# avoccado-avr-pcb-faye.net
KiCad netlist of a schematic drawn in EAGLE
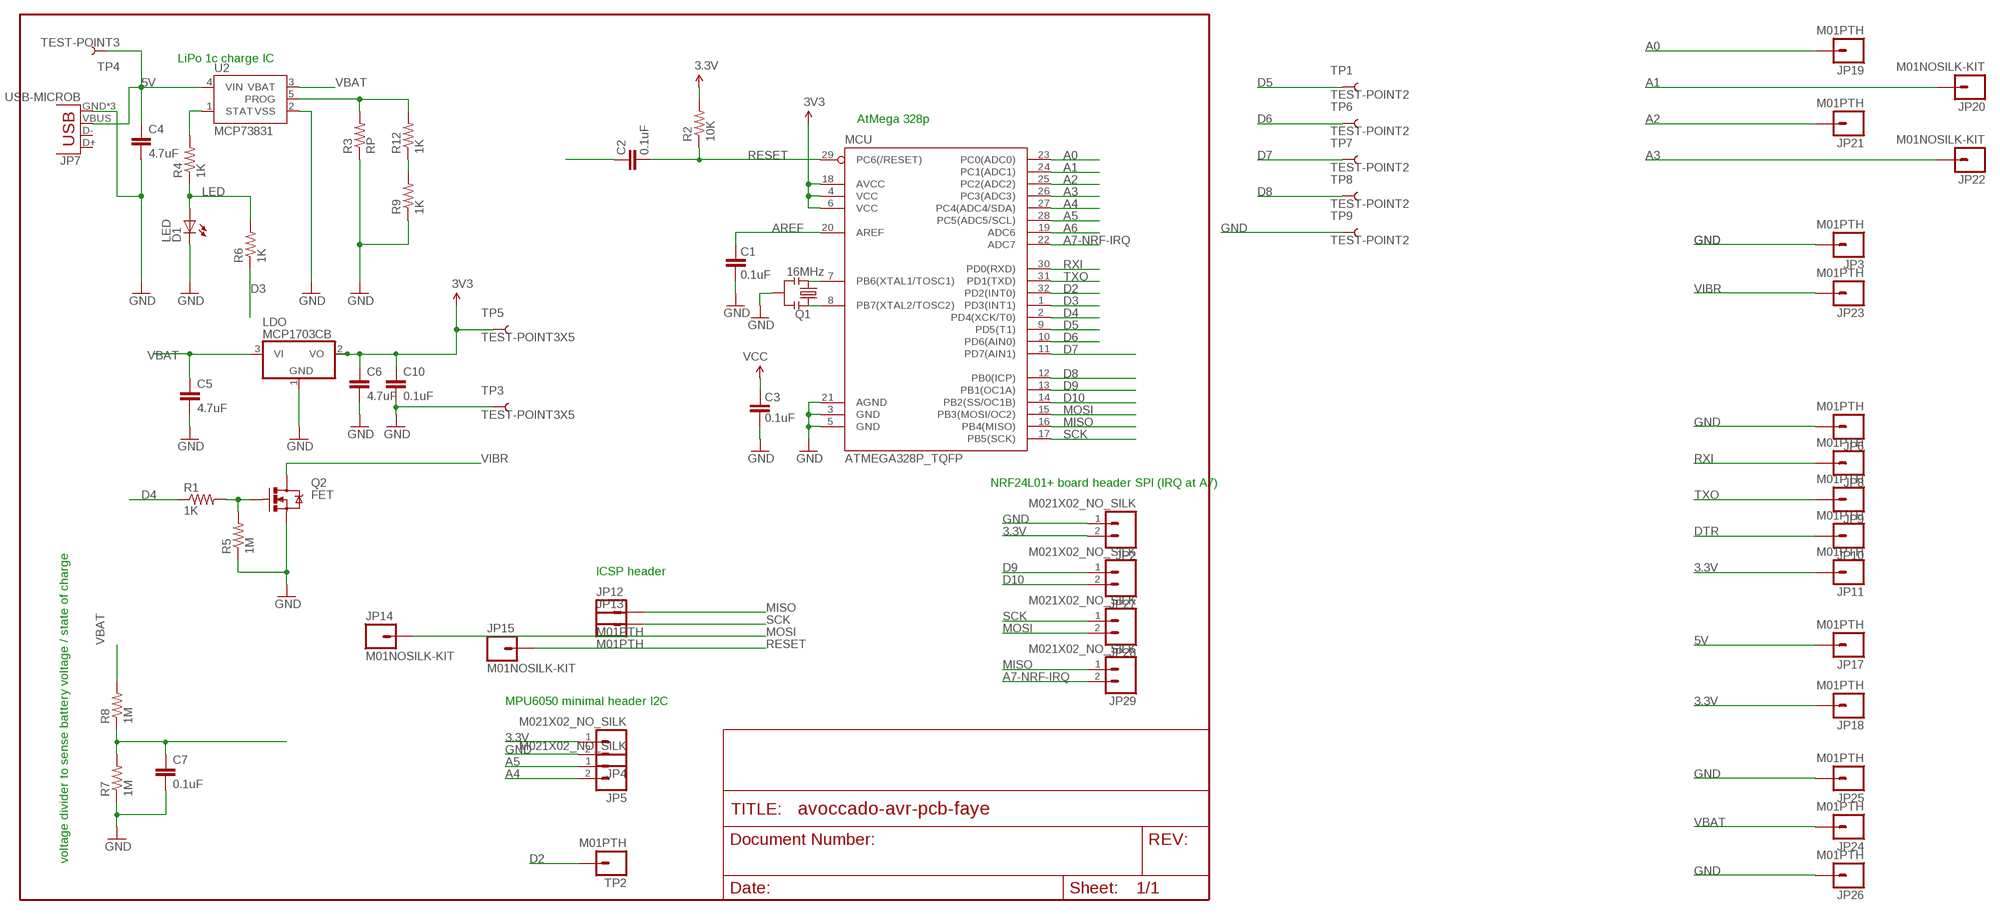
[diagram p0: schematic, sheet 1]

(export (version "E")
  (design (tool "Eeschema 10.0.6"))
  (components
    (comp (ref "C1")
      (value "0.1uF")
      (footprint "eagle-import:C0402")
      (libsource (lib "eagle-import") (part "CAP0402"))
    )
    (comp (ref "C2")
      (value "0.1uF")
      (footprint "eagle-import:C0402")
      (libsource (lib "eagle-import") (part "CAP0402"))
    )
    (comp (ref "C3")
      (value "0.1uF")
      (footprint "eagle-import:C0402")
      (libsource (lib "eagle-import") (part "CAP0402"))
    )
    (comp (ref "C4")
      (value "4.7uF")
      (footprint "eagle-import:0603-CAP")
      (libsource (lib "eagle-import") (part "4.7UF-6.3V-10%(0603)0603"))
    )
    (comp (ref "C5")
      (value "4.7uF")
      (footprint "eagle-import:0603-CAP")
      (libsource (lib "eagle-import") (part "4.7UF-6.3V-10%(0603)0603"))
    )
    (comp (ref "C6")
      (value "4.7uF")
      (footprint "eagle-import:0603-CAP")
      (libsource (lib "eagle-import") (part "4.7UF-6.3V-10%(0603)0603"))
    )
    (comp (ref "C7")
      (value "0.1uF")
      (footprint "eagle-import:C0402")
      (libsource (lib "eagle-import") (part "CAP0402"))
    )
    (comp (ref "C10")
      (value "0.1uF")
      (footprint "eagle-import:C0402")
      (libsource (lib "eagle-import") (part "CAP0402"))
    )
    (comp (ref "D1")
      (value "LED")
      (footprint "eagle-import:LED-0603")
      (libsource (lib "eagle-import") (part "LED0603"))
    )
    (comp (ref "JP2")
      (value "M021X02_NO_SILK")
      (footprint "eagle-import:1X02_NO_SILK")
      (libsource (lib "eagle-import") (part "M021X02_NO_SILK"))
    )
    (comp (ref "JP3")
      (value "M01PTH")
      (footprint "eagle-import:1X01")
      (libsource (lib "eagle-import") (part "M01PTH"))
    )
    (comp (ref "JP4")
      (value "M021X02_NO_SILK")
      (footprint "eagle-import:1X02_NO_SILK")
      (libsource (lib "eagle-import") (part "M021X02_NO_SILK"))
    )
    (comp (ref "JP5")
      (value "M021X02_NO_SILK")
      (footprint "eagle-import:1X02_NO_SILK")
      (libsource (lib "eagle-import") (part "M021X02_NO_SILK"))
    )
    (comp (ref "JP6")
      (value "M01PTH")
      (footprint "eagle-import:1X01")
      (libsource (lib "eagle-import") (part "M01PTH"))
    )
    (comp (ref "JP7")
      (value "USB-MICROB")
      (footprint "eagle-import:USB-MICROB")
      (libsource (lib "eagle-import") (part "USB-MICROB"))
    )
    (comp (ref "JP8")
      (value "M01PTH")
      (footprint "eagle-import:1X01")
      (libsource (lib "eagle-import") (part "M01PTH"))
    )
    (comp (ref "JP9")
      (value "M01PTH")
      (footprint "eagle-import:1X01")
      (libsource (lib "eagle-import") (part "M01PTH"))
    )
    (comp (ref "JP10")
      (value "M01PTH")
      (footprint "eagle-import:1X01")
      (libsource (lib "eagle-import") (part "M01PTH"))
    )
    (comp (ref "JP11")
      (value "M01PTH")
      (footprint "eagle-import:1X01")
      (libsource (lib "eagle-import") (part "M01PTH"))
    )
    (comp (ref "JP12")
      (value "M01PTH")
      (footprint "eagle-import:1X01")
      (libsource (lib "eagle-import") (part "M01PTH"))
    )
    (comp (ref "JP13")
      (value "M01PTH")
      (footprint "eagle-import:1X01")
      (libsource (lib "eagle-import") (part "M01PTH"))
    )
    (comp (ref "JP14")
      (value "M01NOSILK-KIT")
      (footprint "eagle-import:1X01NS-KIT")
      (libsource (lib "eagle-import") (part "M01NOSILK-KIT"))
    )
    (comp (ref "JP15")
      (value "M01NOSILK-KIT")
      (footprint "eagle-import:1X01NS-KIT")
      (libsource (lib "eagle-import") (part "M01NOSILK-KIT"))
    )
    (comp (ref "JP17")
      (value "M01PTH")
      (footprint "eagle-import:1X01")
      (libsource (lib "eagle-import") (part "M01PTH"))
    )
    (comp (ref "JP18")
      (value "M01PTH")
      (footprint "eagle-import:1X01")
      (libsource (lib "eagle-import") (part "M01PTH"))
    )
    (comp (ref "JP19")
      (value "M01PTH")
      (footprint "eagle-import:1X01")
      (libsource (lib "eagle-import") (part "M01PTH"))
    )
    (comp (ref "JP20")
      (value "M01NOSILK-KIT")
      (footprint "eagle-import:1X01NS-KIT")
      (libsource (lib "eagle-import") (part "M01NOSILK-KIT"))
    )
    (comp (ref "JP21")
      (value "M01PTH")
      (footprint "eagle-import:1X01")
      (libsource (lib "eagle-import") (part "M01PTH"))
    )
    (comp (ref "JP22")
      (value "M01NOSILK-KIT")
      (footprint "eagle-import:1X01NS-KIT")
      (libsource (lib "eagle-import") (part "M01NOSILK-KIT"))
    )
    (comp (ref "JP23")
      (value "M01PTH")
      (footprint "eagle-import:1X01")
      (libsource (lib "eagle-import") (part "M01PTH"))
    )
    (comp (ref "JP24")
      (value "M01PTH")
      (footprint "eagle-import:1X01")
      (libsource (lib "eagle-import") (part "M01PTH"))
    )
    (comp (ref "JP25")
      (value "M01PTH")
      (footprint "eagle-import:1X01")
      (libsource (lib "eagle-import") (part "M01PTH"))
    )
    (comp (ref "JP26")
      (value "M01PTH")
      (footprint "eagle-import:1X01")
      (libsource (lib "eagle-import") (part "M01PTH"))
    )
    (comp (ref "JP27")
      (value "M021X02_NO_SILK")
      (footprint "eagle-import:1X02_NO_SILK")
      (libsource (lib "eagle-import") (part "M021X02_NO_SILK"))
    )
    (comp (ref "JP28")
      (value "M021X02_NO_SILK")
      (footprint "eagle-import:1X02_NO_SILK")
      (libsource (lib "eagle-import") (part "M021X02_NO_SILK"))
    )
    (comp (ref "JP29")
      (value "M021X02_NO_SILK")
      (footprint "eagle-import:1X02_NO_SILK")
      (libsource (lib "eagle-import") (part "M021X02_NO_SILK"))
    )
    (comp (ref "LDO")
      (value "MCP1703CB")
      (footprint "eagle-import:SOT23")
      (libsource (lib "eagle-import") (part "MCP1703CB"))
    )
    (comp (ref "MCU")
      (value "ATMEGA328P_TQFP")
      (footprint "eagle-import:TQFP32-08")
      (libsource (lib "eagle-import") (part "ATMEGA328P_TQFP"))
    )
    (comp (ref "Q1")
      (value "16MHz")
      (footprint "eagle-import:RESONATOR-SMD")
      (libsource (lib "eagle-import") (part "RESONATORSMD"))
    )
    (comp (ref "Q2")
      (value "FET")
      (footprint "eagle-import:SOT23-3")
      (libsource (lib "eagle-import") (part "MOSFET-NCHANNELBSS123LT1G"))
    )
    (comp (ref "R1")
      (value "1K")
      (footprint "eagle-import:0603-RES")
      (libsource (lib "eagle-import") (part "RESISTOR0603"))
    )
    (comp (ref "R2")
      (value "10K")
      (footprint "eagle-import:0603-RES")
      (libsource (lib "eagle-import") (part "RESISTOR0603"))
    )
    (comp (ref "R3")
      (value "RP")
      (footprint "eagle-import:0603-RES")
      (libsource (lib "eagle-import") (part "RESISTOR0603"))
    )
    (comp (ref "R4")
      (value "1K")
      (footprint "eagle-import:0603-RES")
      (libsource (lib "eagle-import") (part "RESISTOR0603"))
    )
    (comp (ref "R5")
      (value "1M")
      (footprint "eagle-import:0603-RES")
      (libsource (lib "eagle-import") (part "RESISTOR0603"))
    )
    (comp (ref "R6")
      (value "1K")
      (footprint "eagle-import:0603-RES")
      (libsource (lib "eagle-import") (part "RESISTOR0603"))
    )
    (comp (ref "R7")
      (value "1M")
      (footprint "eagle-import:0603-RES")
      (libsource (lib "eagle-import") (part "RESISTOR0603"))
    )
    (comp (ref "R8")
      (value "1M")
      (footprint "eagle-import:0603-RES")
      (libsource (lib "eagle-import") (part "RESISTOR0603"))
    )
    (comp (ref "R9")
      (value "1K")
      (footprint "eagle-import:0402-RES")
      (libsource (lib "eagle-import") (part "RESISTOR0402"))
    )
    (comp (ref "R12")
      (value "1K")
      (footprint "eagle-import:0402-RES")
      (libsource (lib "eagle-import") (part "RESISTOR0402"))
    )
    (comp (ref "TP1")
      (value "TEST-POINT2")
      (footprint "eagle-import:PAD.02X.02")
      (libsource (lib "eagle-import") (part "TEST-POINT2"))
    )
    (comp (ref "TP2")
      (value "M01PTH")
      (footprint "eagle-import:1X01")
      (libsource (lib "eagle-import") (part "M01PTH"))
    )
    (comp (ref "TP3")
      (value "TEST-POINT3X5")
      (footprint "eagle-import:PAD.03X.05")
      (libsource (lib "eagle-import") (part "TEST-POINT3X5"))
    )
    (comp (ref "TP4")
      (value "TEST-POINT3")
      (footprint "eagle-import:PAD.03X.03")
      (libsource (lib "eagle-import") (part "TEST-POINT3"))
    )
    (comp (ref "TP5")
      (value "TEST-POINT3X5")
      (footprint "eagle-import:PAD.03X.05")
      (libsource (lib "eagle-import") (part "TEST-POINT3X5"))
    )
    (comp (ref "TP6")
      (value "TEST-POINT2")
      (footprint "eagle-import:PAD.02X.02")
      (libsource (lib "eagle-import") (part "TEST-POINT2"))
    )
    (comp (ref "TP7")
      (value "TEST-POINT2")
      (footprint "eagle-import:PAD.02X.02")
      (libsource (lib "eagle-import") (part "TEST-POINT2"))
    )
    (comp (ref "TP8")
      (value "TEST-POINT2")
      (footprint "eagle-import:PAD.02X.02")
      (libsource (lib "eagle-import") (part "TEST-POINT2"))
    )
    (comp (ref "TP9")
      (value "TEST-POINT2")
      (footprint "eagle-import:PAD.02X.02")
      (libsource (lib "eagle-import") (part "TEST-POINT2"))
    )
    (comp (ref "U2")
      (value "MCP73831")
      (footprint "eagle-import:SOT23-5")
      (libsource (lib "eagle-import") (part "MCP73831"))
    )
  )
  (nets
    (net (code "1") (name "/5V") (class "Default")
      (node (ref "C4") (pin "1") (pinfunction "1_1") (pintype "passive"))
      (node (ref "JP17") (pin "1") (pinfunction "1_1") (pintype "passive"))
      (node (ref "JP7") (pin "VBUS") (pinfunction "VBUS_VBUS") (pintype "bidirectional"))
      (node (ref "TP4") (pin "P$1") (pinfunction "1_P$1") (pintype "bidirectional"))
      (node (ref "U2") (pin "4") (pinfunction "VIN_4") (pintype "power_in"))
    )
    (net (code "2") (name "/A0") (class "Default")
      (node (ref "JP19") (pin "1") (pinfunction "1_1") (pintype "passive"))
      (node (ref "MCU") (pin "23") (pinfunction "PC0(ADC0)_23") (pintype "bidirectional"))
    )
    (net (code "3") (name "/A1") (class "Default")
      (node (ref "JP20") (pin "1") (pinfunction "1_1") (pintype "passive"))
      (node (ref "MCU") (pin "24") (pinfunction "PC1(ADC1)_24") (pintype "bidirectional"))
    )
    (net (code "4") (name "/A2") (class "Default")
      (node (ref "JP21") (pin "1") (pinfunction "1_1") (pintype "passive"))
      (node (ref "MCU") (pin "25") (pinfunction "PC2(ADC2)_25") (pintype "bidirectional"))
    )
    (net (code "5") (name "/A3") (class "Default")
      (node (ref "C7") (pin "1") (pinfunction "1_1") (pintype "passive"))
      (node (ref "JP22") (pin "1") (pinfunction "1_1") (pintype "passive"))
      (node (ref "MCU") (pin "26") (pinfunction "PC3(ADC3)_26") (pintype "bidirectional"))
      (node (ref "R7") (pin "2") (pinfunction "2_2") (pintype "passive"))
      (node (ref "R8") (pin "1") (pinfunction "1_1") (pintype "passive"))
    )
    (net (code "6") (name "/A4") (class "Default")
      (node (ref "JP5") (pin "2") (pinfunction "2_2") (pintype "passive"))
      (node (ref "MCU") (pin "27") (pinfunction "PC4(ADC4/SDA)_27") (pintype "bidirectional"))
    )
    (net (code "7") (name "/A5") (class "Default")
      (node (ref "JP5") (pin "1") (pinfunction "1_1") (pintype "passive"))
      (node (ref "MCU") (pin "28") (pinfunction "PC5(ADC5/SCL)_28") (pintype "bidirectional"))
    )
    (net (code "8") (name "/A6") (class "Default")
      (node (ref "MCU") (pin "19") (pinfunction "ADC6_19") (pintype "bidirectional"))
    )
    (net (code "9") (name "/A7-NRF-IRQ") (class "Default")
      (node (ref "JP29") (pin "2") (pinfunction "2_2") (pintype "passive"))
      (node (ref "MCU") (pin "22") (pinfunction "ADC7_22") (pintype "bidirectional"))
    )
    (net (code "10") (name "/AREF") (class "Default")
      (node (ref "C1") (pin "2") (pinfunction "2_2") (pintype "passive"))
      (node (ref "MCU") (pin "20") (pinfunction "AREF_20") (pintype "bidirectional"))
    )
    (net (code "11") (name "/D2") (class "Default")
      (node (ref "MCU") (pin "32") (pinfunction "PD2(INT0)_32") (pintype "bidirectional"))
      (node (ref "TP2") (pin "1") (pinfunction "1_1") (pintype "passive"))
    )
    (net (code "12") (name "/D3") (class "Default")
      (node (ref "MCU") (pin "1") (pinfunction "PD3(INT1)_1") (pintype "bidirectional"))
      (node (ref "R6") (pin "1") (pinfunction "1_1") (pintype "passive"))
    )
    (net (code "13") (name "/D4") (class "Default")
      (node (ref "MCU") (pin "2") (pinfunction "PD4(XCK/T0)_2") (pintype "bidirectional"))
      (node (ref "R1") (pin "1") (pinfunction "1_1") (pintype "passive"))
    )
    (net (code "14") (name "/D5") (class "Default")
      (node (ref "MCU") (pin "9") (pinfunction "PD5(T1)_9") (pintype "bidirectional"))
      (node (ref "TP1") (pin "P$1") (pinfunction "1_P$1") (pintype "bidirectional"))
    )
    (net (code "15") (name "/D6") (class "Default")
      (node (ref "MCU") (pin "10") (pinfunction "PD6(AIN0)_10") (pintype "bidirectional"))
      (node (ref "TP6") (pin "P$1") (pinfunction "1_P$1") (pintype "bidirectional"))
    )
    (net (code "16") (name "/D7") (class "Default")
      (node (ref "MCU") (pin "11") (pinfunction "PD7(AIN1)_11") (pintype "bidirectional"))
      (node (ref "TP7") (pin "P$1") (pinfunction "1_P$1") (pintype "bidirectional"))
    )
    (net (code "17") (name "/D8") (class "Default")
      (node (ref "MCU") (pin "12") (pinfunction "PB0(ICP)_12") (pintype "bidirectional"))
      (node (ref "TP8") (pin "P$1") (pinfunction "1_P$1") (pintype "bidirectional"))
    )
    (net (code "18") (name "/D9") (class "Default")
      (node (ref "JP27") (pin "1") (pinfunction "1_1") (pintype "passive"))
      (node (ref "MCU") (pin "13") (pinfunction "PB1(OC1A)_13") (pintype "bidirectional"))
    )
    (net (code "19") (name "/D10") (class "Default")
      (node (ref "JP27") (pin "2") (pinfunction "2_2") (pintype "passive"))
      (node (ref "MCU") (pin "14") (pinfunction "PB2(SS/OC1B)_14") (pintype "bidirectional"))
    )
    (net (code "20") (name "/DTR") (class "Default")
      (node (ref "C2") (pin "2") (pinfunction "2_2") (pintype "passive"))
      (node (ref "JP10") (pin "1") (pinfunction "1_1") (pintype "passive"))
    )
    (net (code "21") (name "/LED") (class "Default")
      (node (ref "D1") (pin "A") (pinfunction "A_A") (pintype "passive"))
      (node (ref "R4") (pin "1") (pinfunction "1_1") (pintype "passive"))
      (node (ref "R6") (pin "2") (pinfunction "2_2") (pintype "passive"))
    )
    (net (code "22") (name "/MISO") (class "Default")
      (node (ref "JP12") (pin "1") (pinfunction "1_1") (pintype "passive"))
      (node (ref "JP29") (pin "1") (pinfunction "1_1") (pintype "passive"))
      (node (ref "MCU") (pin "16") (pinfunction "PB4(MISO)_16") (pintype "bidirectional"))
    )
    (net (code "23") (name "/MOSI") (class "Default")
      (node (ref "JP14") (pin "1") (pinfunction "1_1") (pintype "passive"))
      (node (ref "JP28") (pin "2") (pinfunction "2_2") (pintype "passive"))
      (node (ref "MCU") (pin "15") (pinfunction "PB3(MOSI/OC2)_15") (pintype "bidirectional"))
    )
    (net (code "24") (name "/RESET") (class "Default")
      (node (ref "C2") (pin "1") (pinfunction "1_1") (pintype "passive"))
      (node (ref "JP15") (pin "1") (pinfunction "1_1") (pintype "passive"))
      (node (ref "MCU") (pin "29") (pinfunction "PC6(/RESET)_29") (pintype "bidirectional"))
      (node (ref "R2") (pin "1") (pinfunction "1_1") (pintype "passive"))
    )
    (net (code "25") (name "/RXI") (class "Default")
      (node (ref "JP8") (pin "1") (pinfunction "1_1") (pintype "passive"))
      (node (ref "MCU") (pin "30") (pinfunction "PD0(RXD)_30") (pintype "bidirectional"))
    )
    (net (code "26") (name "/SCK") (class "Default")
      (node (ref "JP13") (pin "1") (pinfunction "1_1") (pintype "passive"))
      (node (ref "JP28") (pin "1") (pinfunction "1_1") (pintype "passive"))
      (node (ref "MCU") (pin "17") (pinfunction "PB5(SCK)_17") (pintype "bidirectional"))
    )
    (net (code "27") (name "/TXO") (class "Default")
      (node (ref "JP9") (pin "1") (pinfunction "1_1") (pintype "passive"))
      (node (ref "MCU") (pin "31") (pinfunction "PD1(TXD)_31") (pintype "bidirectional"))
    )
    (net (code "28") (name "/VBAT") (class "Default")
      (node (ref "C5") (pin "1") (pinfunction "1_1") (pintype "passive"))
      (node (ref "JP24") (pin "1") (pinfunction "1_1") (pintype "passive"))
      (node (ref "LDO") (pin "3") (pinfunction "VI_3") (pintype "input"))
      (node (ref "R8") (pin "2") (pinfunction "2_2") (pintype "passive"))
      (node (ref "U2") (pin "3") (pinfunction "VBAT_3") (pintype "power_in"))
    )
    (net (code "29") (name "/VIBR") (class "Default")
      (node (ref "JP23") (pin "1") (pinfunction "1_1") (pintype "passive"))
      (node (ref "Q2") (pin "3") (pinfunction "D_3") (pintype "passive"))
    )
    (net (code "30") (name "3.3V") (class "Default")
      (node (ref "C10") (pin "1") (pinfunction "1_1") (pintype "passive"))
      (node (ref "C3") (pin "2") (pinfunction "2_2") (pintype "passive"))
      (node (ref "C6") (pin "1") (pinfunction "1_1") (pintype "passive"))
      (node (ref "JP11") (pin "1") (pinfunction "1_1") (pintype "passive"))
      (node (ref "JP18") (pin "1") (pinfunction "1_1") (pintype "passive"))
      (node (ref "JP2") (pin "2") (pinfunction "2_2") (pintype "passive"))
      (node (ref "JP4") (pin "1") (pinfunction "1_1") (pintype "passive"))
      (node (ref "LDO") (pin "2") (pinfunction "VO_2") (pintype "passive"))
      (node (ref "MCU") (pin "18") (pinfunction "AVCC_18") (pintype "bidirectional"))
      (node (ref "MCU") (pin "4") (pinfunction "VCC_4") (pintype "bidirectional"))
      (node (ref "MCU") (pin "6") (pinfunction "VCC_6") (pintype "bidirectional"))
      (node (ref "R2") (pin "2") (pinfunction "2_2") (pintype "passive"))
      (node (ref "TP5") (pin "P$1") (pinfunction "1_P$1") (pintype "bidirectional"))
    )
    (net (code "31") (name "GND") (class "Default")
      (node (ref "C1") (pin "1") (pinfunction "1_1") (pintype "passive"))
      (node (ref "C10") (pin "2") (pinfunction "2_2") (pintype "passive"))
      (node (ref "C3") (pin "1") (pinfunction "1_1") (pintype "passive"))
      (node (ref "C4") (pin "2") (pinfunction "2_2") (pintype "passive"))
      (node (ref "C5") (pin "2") (pinfunction "2_2") (pintype "passive"))
      (node (ref "C6") (pin "2") (pinfunction "2_2") (pintype "passive"))
      (node (ref "C7") (pin "2") (pinfunction "2_2") (pintype "passive"))
      (node (ref "D1") (pin "C") (pinfunction "C_C") (pintype "passive"))
      (node (ref "JP2") (pin "1") (pinfunction "1_1") (pintype "passive"))
      (node (ref "JP25") (pin "1") (pinfunction "1_1") (pintype "passive"))
      (node (ref "JP26") (pin "1") (pinfunction "1_1") (pintype "passive"))
      (node (ref "JP3") (pin "1") (pinfunction "1_1") (pintype "passive"))
      (node (ref "JP4") (pin "2") (pinfunction "2_2") (pintype "passive"))
      (node (ref "JP6") (pin "1") (pinfunction "1_1") (pintype "passive"))
      (node (ref "JP7") (pin "GND") (pinfunction "GND_GND") (pintype "bidirectional"))
      (node (ref "JP7") (pin "MT1") (pinfunction "GND_MT1") (pintype "bidirectional"))
      (node (ref "JP7") (pin "MT2") (pinfunction "GND_MT2") (pintype "bidirectional"))
      (node (ref "LDO") (pin "1") (pinfunction "GND_1") (pintype "passive"))
      (node (ref "MCU") (pin "21") (pinfunction "AGND_21") (pintype "bidirectional"))
      (node (ref "MCU") (pin "3") (pinfunction "GND_3") (pintype "bidirectional"))
      (node (ref "MCU") (pin "5") (pinfunction "GND_5") (pintype "bidirectional"))
      (node (ref "Q1") (pin "2") (pinfunction "2_2") (pintype "passive"))
      (node (ref "Q2") (pin "2") (pinfunction "S_2") (pintype "passive"))
      (node (ref "R3") (pin "1") (pinfunction "1_1") (pintype "passive"))
      (node (ref "R5") (pin "1") (pinfunction "1_1") (pintype "passive"))
      (node (ref "R7") (pin "1") (pinfunction "1_1") (pintype "passive"))
      (node (ref "R9") (pin "1") (pinfunction "1_1") (pintype "passive"))
      (node (ref "TP3") (pin "P$1") (pinfunction "1_P$1") (pintype "bidirectional"))
      (node (ref "TP9") (pin "P$1") (pinfunction "1_P$1") (pintype "bidirectional"))
      (node (ref "U2") (pin "2") (pinfunction "VSS_2") (pintype "power_in"))
    )
    (net (code "32") (name "Net-(MCU-PB6(XTAL1{slash}TOSC1))") (class "Default")
      (node (ref "MCU") (pin "7") (pinfunction "PB6(XTAL1/TOSC1)_7") (pintype "bidirectional"))
      (node (ref "Q1") (pin "3") (pinfunction "3_3") (pintype "passive"))
    )
    (net (code "33") (name "Net-(MCU-PB7(XTAL2{slash}TOSC2))") (class "Default")
      (node (ref "MCU") (pin "8") (pinfunction "PB7(XTAL2/TOSC2)_8") (pintype "bidirectional"))
      (node (ref "Q1") (pin "1") (pinfunction "1_1") (pintype "passive"))
    )
    (net (code "34") (name "Net-(Q2-G)") (class "Default")
      (node (ref "Q2") (pin "1") (pinfunction "G_1") (pintype "passive"))
      (node (ref "R1") (pin "2") (pinfunction "2_2") (pintype "passive"))
      (node (ref "R5") (pin "2") (pinfunction "2_2") (pintype "passive"))
    )
    (net (code "35") (name "Net-(R12-Pad1)") (class "Default")
      (node (ref "R12") (pin "1") (pinfunction "1_1") (pintype "passive"))
      (node (ref "R9") (pin "2") (pinfunction "2_2") (pintype "passive"))
    )
    (net (code "36") (name "Net-(U2-PROG)") (class "Default")
      (node (ref "R12") (pin "2") (pinfunction "2_2") (pintype "passive"))
      (node (ref "R3") (pin "2") (pinfunction "2_2") (pintype "passive"))
      (node (ref "U2") (pin "5") (pinfunction "PROG_5") (pintype "input"))
    )
    (net (code "37") (name "Net-(U2-STAT)") (class "Default")
      (node (ref "R4") (pin "2") (pinfunction "2_2") (pintype "passive"))
      (node (ref "U2") (pin "1") (pinfunction "STAT_1") (pintype "output"))
    )
    (net (code "38") (name "unconnected-(JP7-PadD+)") (class "Default")
      (node (ref "JP7") (pin "D+") (pinfunction "D+_D+") (pintype "bidirectional"))
    )
    (net (code "39") (name "unconnected-(JP7-PadD-)") (class "Default")
      (node (ref "JP7") (pin "D-") (pinfunction "D-_D-") (pintype "bidirectional"))
    )
  )
)
